# d11toy1.net
KiCad netlist of a schematic drawn in EAGLE
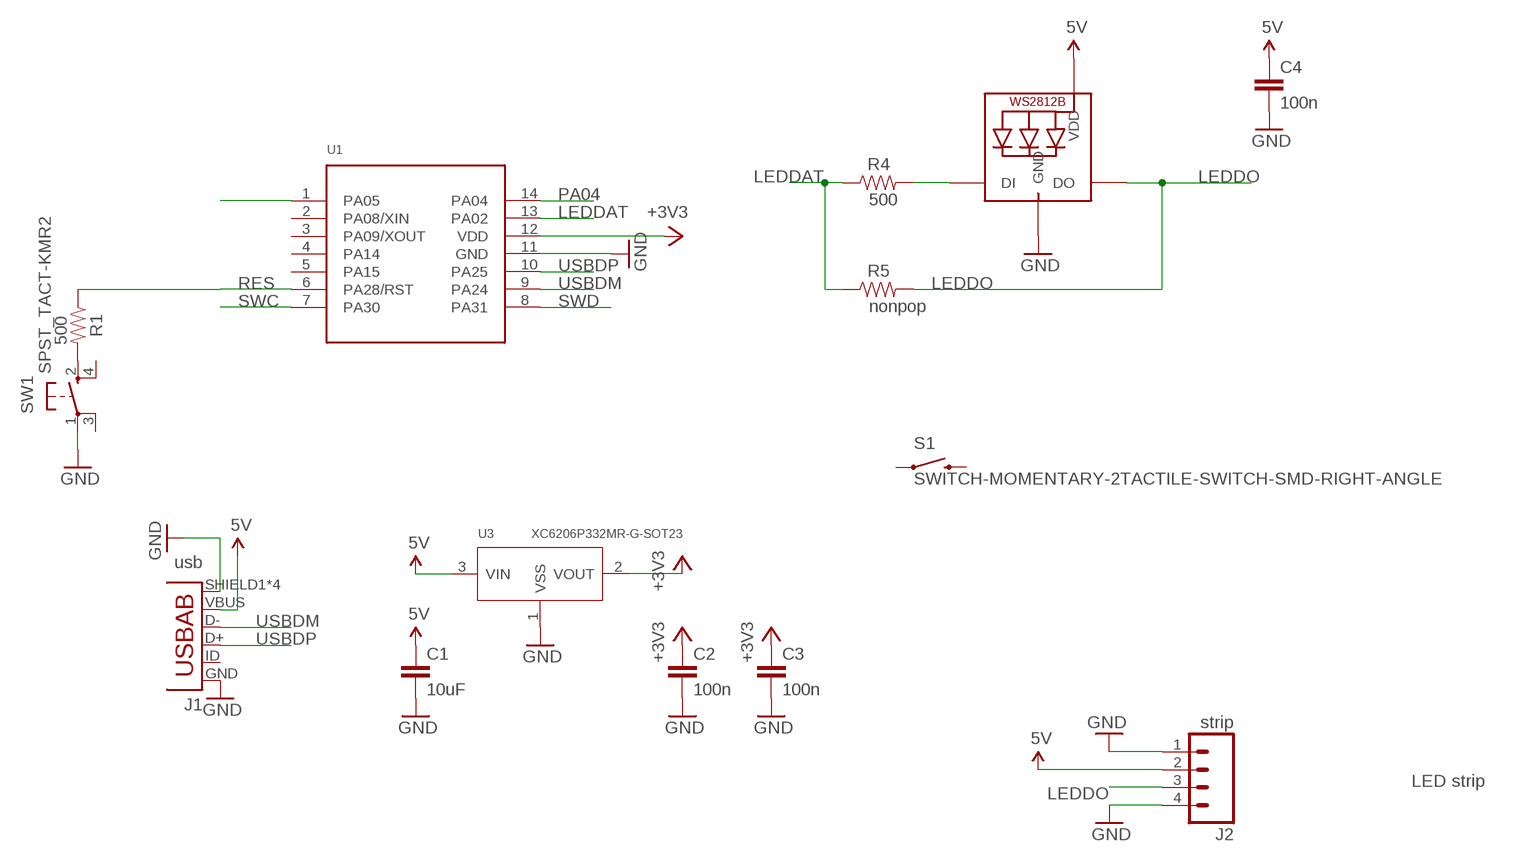
[diagram p0: schematic, sheet 1]

(export (version "E")
  (design (tool "Eeschema 10.0.6"))
  (components
    (comp (ref "C1")
      (value "10uF")
      (footprint "eagle-import:0603-CAP")
      (libsource (lib "eagle-import") (part "CAP0603-CAP"))
    )
    (comp (ref "C2")
      (value "100n")
      (footprint "eagle-import:0603-CAP")
      (libsource (lib "eagle-import") (part "CAP0603-CAP"))
    )
    (comp (ref "C3")
      (value "100n")
      (footprint "eagle-import:0603-CAP")
      (libsource (lib "eagle-import") (part "CAP0603-CAP"))
    )
    (comp (ref "C4")
      (value "100n")
      (footprint "eagle-import:0603-CAP")
      (libsource (lib "eagle-import") (part "CAP0603-CAP"))
    )
    (comp (ref "J1")
      (value "usb")
      (footprint "eagle-import:USB-AB-MICRO-SMD")
      (libsource (lib "eagle-import") (part "USB-AB"))
    )
    (comp (ref "J2")
      (value "strip")
      (footprint "eagle-import:1X04_NO_SILK_ALL_ROUND")
      (libsource (lib "eagle-import") (part "M04NO_SILK_ALL_ROUND"))
    )
    (comp (ref "LED1")
      (value "WS2812B3535")
      (footprint "eagle-import:LED3535")
      (libsource (lib "eagle-import") (part "WS2812B3535"))
    )
    (comp (ref "R1")
      (value "500")
      (footprint "eagle-import:0603-RES")
      (libsource (lib "eagle-import") (part "RESISTOR0603-RES"))
    )
    (comp (ref "R4")
      (value "500")
      (footprint "eagle-import:0603-RES")
      (libsource (lib "eagle-import") (part "RESISTOR0603-RES"))
    )
    (comp (ref "R5")
      (value "nonpop")
      (footprint "eagle-import:0603-RES")
      (libsource (lib "eagle-import") (part "RESISTOR0603-RES"))
    )
    (comp (ref "S1")
      (value "SWITCH-MOMENTARY-2TACTILE-SWITCH-SMD-RIGHT-ANGLE")
      (footprint "eagle-import:TACTILE_SWITCH-SMD-RIGHT-ANGLE")
      (libsource (lib "eagle-import") (part "SWITCH-MOMENTARY-2TACTILE-SWITCH-SMD-RIGHT-ANGLE"))
    )
    (comp (ref "SW1")
      (value "SPST_TACT-KMR2")
      (footprint "eagle-import:KMR2")
      (libsource (lib "eagle-import") (part "SPST_TACT-KMR2"))
    )
    (comp (ref "U1")
      (value "SAMD11C14")
      (footprint "eagle-import:SO14")
      (libsource (lib "eagle-import") (part "SAMD11C14"))
    )
    (comp (ref "U3")
      (value "XC6206P332MR-G-SOT23")
      (footprint "eagle-import:SOT-23")
      (fields (field (name "MPN") "XC6206P332MR-G"))
      (libsource (lib "eagle-import") (part "PMIC-LDO-XC6206P332MR-G(SOT23)"))
    )
  )
  (nets
    (net (code "1") (name "+3V3") (class "Default")
      (node (ref "C2") (pin "1") (pinfunction "1_1") (pintype "passive"))
      (node (ref "C3") (pin "1") (pinfunction "1_1") (pintype "passive"))
      (node (ref "U1") (pin "12") (pinfunction "VDD_12") (pintype "bidirectional"))
      (node (ref "U3") (pin "2") (pinfunction "VOUT_2") (pintype "output"))
    )
    (net (code "2") (name "/LEDDAT") (class "Default")
      (node (ref "R4") (pin "1") (pinfunction "1_1") (pintype "passive"))
      (node (ref "R5") (pin "1") (pinfunction "1_1") (pintype "passive"))
      (node (ref "U1") (pin "13") (pinfunction "PA02_13") (pintype "bidirectional"))
    )
    (net (code "3") (name "/LEDDO") (class "Default")
      (node (ref "J2") (pin "3") (pinfunction "3_3") (pintype "passive"))
      (node (ref "LED1") (pin "3") (pinfunction "DO_3") (pintype "output"))
      (node (ref "R5") (pin "2") (pinfunction "2_2") (pintype "passive"))
    )
    (net (code "4") (name "/PA04") (class "Default")
      (node (ref "U1") (pin "14") (pinfunction "PA04_14") (pintype "bidirectional"))
    )
    (net (code "5") (name "/RES") (class "Default")
      (node (ref "R1") (pin "1") (pinfunction "1_1") (pintype "passive"))
      (node (ref "U1") (pin "6") (pinfunction "PA28/RST_6") (pintype "bidirectional"))
    )
    (net (code "6") (name "/SWC") (class "Default")
      (node (ref "U1") (pin "7") (pinfunction "PA30_7") (pintype "bidirectional"))
    )
    (net (code "7") (name "/SWD") (class "Default")
      (node (ref "U1") (pin "8") (pinfunction "PA31_8") (pintype "bidirectional"))
    )
    (net (code "8") (name "/USBDM") (class "Default")
      (node (ref "J1") (pin "D-") (pinfunction "D-_D-") (pintype "bidirectional"))
      (node (ref "U1") (pin "9") (pinfunction "PA24_9") (pintype "bidirectional"))
    )
    (net (code "9") (name "/USBDP") (class "Default")
      (node (ref "J1") (pin "D+") (pinfunction "D+_D+") (pintype "bidirectional"))
      (node (ref "U1") (pin "10") (pinfunction "PA25_10") (pintype "bidirectional"))
    )
    (net (code "10") (name "5V") (class "Default")
      (node (ref "C1") (pin "1") (pinfunction "1_1") (pintype "passive"))
      (node (ref "C4") (pin "1") (pinfunction "1_1") (pintype "passive"))
      (node (ref "J1") (pin "VBUS") (pinfunction "VBUS_VBUS") (pintype "bidirectional"))
      (node (ref "J2") (pin "2") (pinfunction "2_2") (pintype "passive"))
      (node (ref "LED1") (pin "2") (pinfunction "VDD_2") (pintype "power_in"))
      (node (ref "U3") (pin "3") (pinfunction "VIN_3") (pintype "input"))
    )
    (net (code "11") (name "GND") (class "Default")
      (node (ref "C1") (pin "2") (pinfunction "2_2") (pintype "passive"))
      (node (ref "C2") (pin "2") (pinfunction "2_2") (pintype "passive"))
      (node (ref "C3") (pin "2") (pinfunction "2_2") (pintype "passive"))
      (node (ref "C4") (pin "2") (pinfunction "2_2") (pintype "passive"))
      (node (ref "J1") (pin "GND") (pinfunction "GND_GND") (pintype "bidirectional"))
      (node (ref "J1") (pin "SHIELD1") (pinfunction "SHIELD_SHIELD1") (pintype "bidirectional"))
      (node (ref "J1") (pin "SHIELD2") (pinfunction "SHIELD_SHIELD2") (pintype "bidirectional"))
      (node (ref "J1") (pin "SHIELD3") (pinfunction "SHIELD_SHIELD3") (pintype "bidirectional"))
      (node (ref "J1") (pin "SHIELD4") (pinfunction "SHIELD_SHIELD4") (pintype "bidirectional"))
      (node (ref "J2") (pin "1") (pinfunction "1_1") (pintype "passive"))
      (node (ref "J2") (pin "4") (pinfunction "4_4") (pintype "passive"))
      (node (ref "LED1") (pin "4") (pinfunction "GND_4") (pintype "power_in"))
      (node (ref "SW1") (pin "1") (pinfunction "P_1") (pintype "passive"))
      (node (ref "U1") (pin "11") (pinfunction "GND_11") (pintype "bidirectional"))
      (node (ref "U3") (pin "1") (pinfunction "VSS_1") (pintype "power_in"))
    )
    (net (code "12") (name "Net-(LED1-DI)") (class "Default")
      (node (ref "LED1") (pin "1") (pinfunction "DI_1") (pintype "input"))
      (node (ref "R4") (pin "2") (pinfunction "2_2") (pintype "passive"))
    )
    (net (code "13") (name "Net-(SW1-S)") (class "Default")
      (node (ref "R1") (pin "2") (pinfunction "2_2") (pintype "passive"))
      (node (ref "SW1") (pin "2") (pinfunction "S_2") (pintype "passive"))
    )
    (net (code "14") (name "unconnected-(J1-USBID-PadID)") (class "Default")
      (node (ref "J1") (pin "ID") (pinfunction "USBID_ID") (pintype "bidirectional"))
    )
    (net (code "15") (name "unconnected-(S1-Pad1)") (class "Default")
      (node (ref "S1") (pin "1") (pinfunction "1_1") (pintype "passive"))
    )
    (net (code "16") (name "unconnected-(S1-Pad2)") (class "Default")
      (node (ref "S1") (pin "2") (pinfunction "2_2") (pintype "passive"))
    )
    (net (code "17") (name "unconnected-(SW1-P1-Pad3)") (class "Default")
      (node (ref "SW1") (pin "3") (pinfunction "P1_3") (pintype "passive"))
    )
    (net (code "18") (name "unconnected-(SW1-S1-Pad4)") (class "Default")
      (node (ref "SW1") (pin "4") (pinfunction "S1_4") (pintype "passive"))
    )
    (net (code "19") (name "unconnected-(U1-PA05-Pad1)") (class "Default")
      (node (ref "U1") (pin "1") (pinfunction "PA05_1") (pintype "bidirectional"))
    )
    (net (code "20") (name "unconnected-(U1-PA08{slash}XIN-Pad2)") (class "Default")
      (node (ref "U1") (pin "2") (pinfunction "PA08/XIN_2") (pintype "bidirectional"))
    )
    (net (code "21") (name "unconnected-(U1-PA09{slash}XOUT-Pad3)") (class "Default")
      (node (ref "U1") (pin "3") (pinfunction "PA09/XOUT_3") (pintype "bidirectional"))
    )
    (net (code "22") (name "unconnected-(U1-PA14-Pad4)") (class "Default")
      (node (ref "U1") (pin "4") (pinfunction "PA14_4") (pintype "bidirectional"))
    )
    (net (code "23") (name "unconnected-(U1-PA15-Pad5)") (class "Default")
      (node (ref "U1") (pin "5") (pinfunction "PA15_5") (pintype "bidirectional"))
    )
  )
)
